# Telemetria_Alimenta_o___Reset.net
KiCad netlist of a schematic drawn in Altium Designer
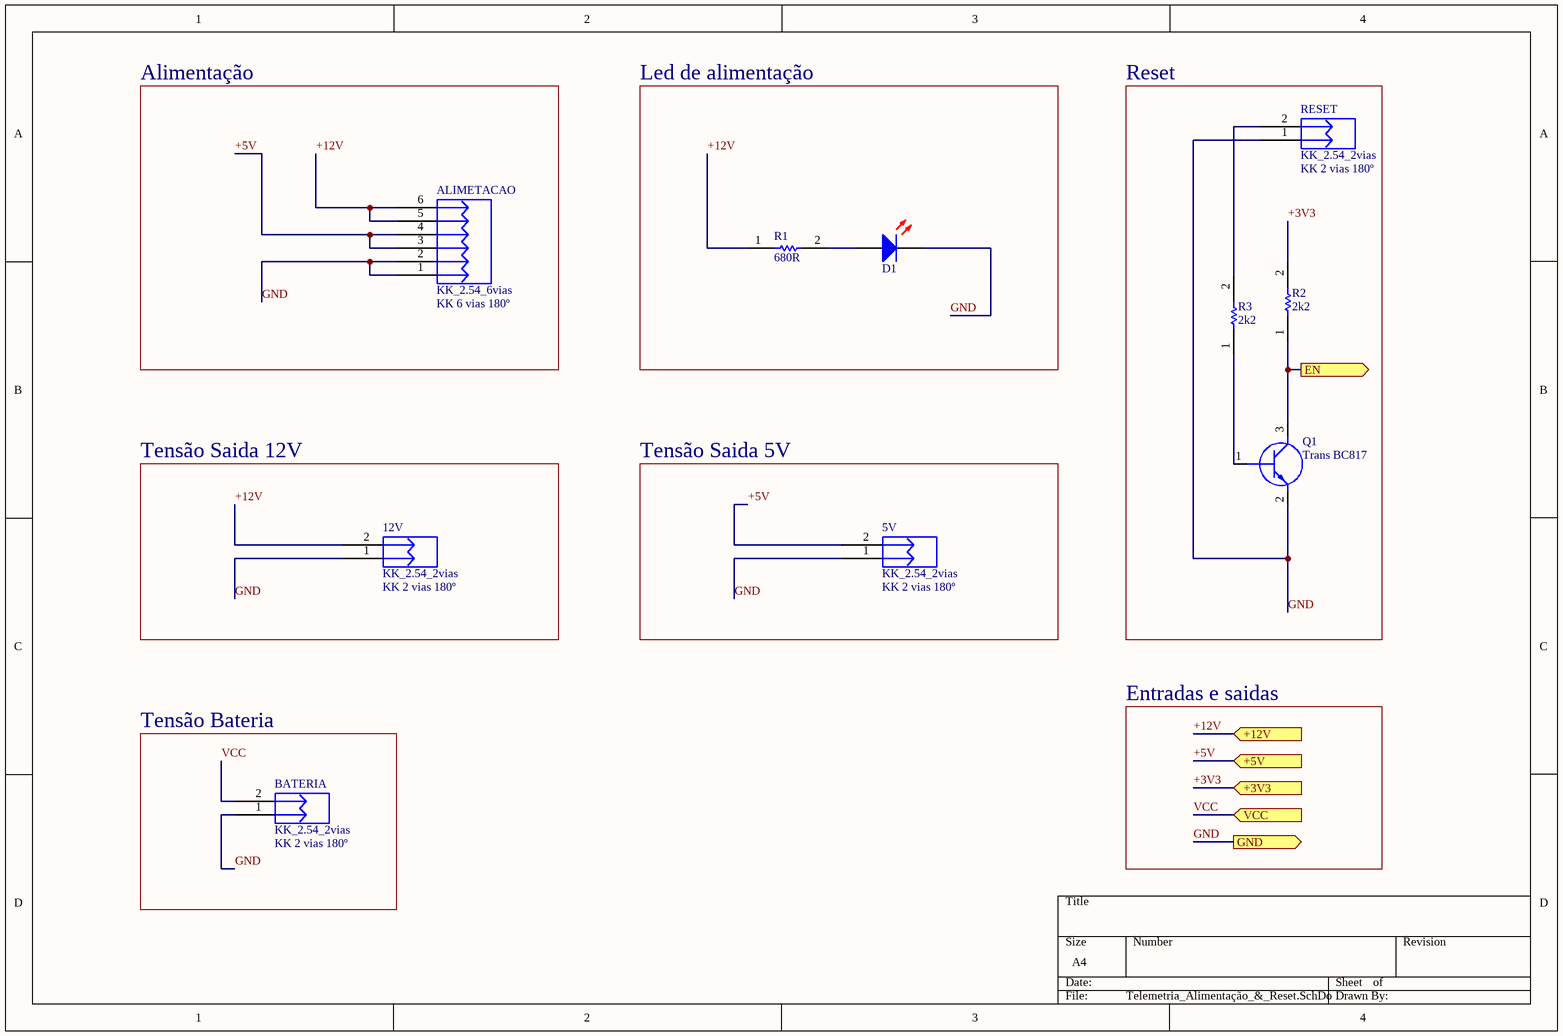
[diagram p0: Telemetria_Alimentação_&_Reset.SchDoc]

(export (version "E")
  (design (tool "Eeschema 10.0.6"))
  (components
    (comp (ref "5V")
      (value "KK_2.54_2vias")
      (footprint "KK_2VIAS_180º")
      (description "Conector KK 2.54mm 2 vias")
      (fields (field (name "VALOR") "KK 2 vias 180º"))
      (libsource (lib "Sinaliza玢o_Official") (part "KK_2.54_2vias"))
    )
    (comp (ref "12V")
      (value "KK_2.54_2vias")
      (footprint "KK_2VIAS_180º")
      (description "Conector KK 2.54mm 2 vias")
      (fields (field (name "VALOR") "KK 2 vias 180º"))
      (libsource (lib "Sinaliza玢o_Official") (part "KK_2.54_2vias"))
    )
    (comp (ref "ALIMETACAO")
      (value "KK_2.54_6vias")
      (footprint "KK_6vias_180°")
      (description "Conector KK 2.54mm 6 vias")
      (fields (field (name "VALOR") "KK 6 vias 180º"))
      (libsource (lib "Sinaliza玢o_Official") (part "KK_2.54_6vias"))
    )
    (comp (ref "BATERIA")
      (value "KK_2.54_2vias")
      (footprint "KK_2VIAS_180º")
      (description "Conector KK 2.54mm 2 vias")
      (fields (field (name "VALOR") "KK 2 vias 180º"))
      (libsource (lib "Conectores_Sch") (part "KK_2.54_2vias"))
    )
    (comp (ref "D1")
      (value "LED 3MM RED")
      (footprint "LED RED")
      (fields (field (name "MANUFACTURER") "Paralight") (field (name "MANUFACTURER PART NUMBER") "IMP585"))
      (libsource (lib "Sinaliza玢o_Official") (part "LED 3MM RED"))
    )
    (comp (ref "Q1")
      (value "Trans BC817")
      (footprint "SOT96P240X110-3N")
      (description "Transistor BJT NPN BC817-25-7-F")
      (fields
        (field (name "MANUFACTURER_PART_NUMBER") "BC817-25-7-F")
        (field (name "MOUSER PART NUMBER") "621-BC817-25-7-F")
      )
      (libsource (lib "Sinaliza玢o_Official") (part "Trans BC817"))
    )
    (comp (ref "R1")
      (value "680R")
      (footprint "RESC3216X60N")
      (description "Resistor")
      (fields
        (field (name "MANUFACTURER_PART_NUMBER") "CRCW12064K70FKEA")
        (field (name "MOUSER PART NUMBER") "71-CRCW1206-4.7K-E3")
      )
      (libsource (lib "Sinaliza玢o_Official") (part "Resistor 1206"))
    )
    (comp (ref "R2")
      (value "2k2")
      (footprint "RESC3216X60N")
      (description "Resistor")
      (fields
        (field (name "MANUFACTURER_PART_NUMBER") "CRCW12064K70FKEA")
        (field (name "MOUSER PART NUMBER") "71-CRCW1206-4.7K-E3")
      )
      (libsource (lib "Sinaliza玢o_Official") (part "Resistor 1206"))
    )
    (comp (ref "R3")
      (value "2k2")
      (footprint "RESC3216X60N")
      (description "Resistor")
      (fields
        (field (name "MANUFACTURER_PART_NUMBER") "CRCW12064K70FKEA")
        (field (name "MOUSER PART NUMBER") "71-CRCW1206-4.7K-E3")
      )
      (libsource (lib "Sinaliza玢o_Official") (part "Resistor 1206"))
    )
    (comp (ref "RESET")
      (value "KK_2.54_2vias")
      (footprint "KK_2VIAS_180º")
      (description "Conector KK 2.54mm 2 vias")
      (fields (field (name "VALOR") "KK 2 vias 180º"))
      (libsource (lib "Sinaliza玢o_Official") (part "KK_2.54_2vias"))
    )
  )
  (nets
    (net (code "1") (name "/+3V3") (class "Default")
      (node (ref "R2") (pin "2") (pinfunction "2_2") (pintype "passive"))
    )
    (net (code "2") (name "/+5V") (class "Default")
      (node (ref "5V") (pin "2") (pintype "passive"))
      (node (ref "ALIMETACAO") (pin "3") (pintype "passive"))
      (node (ref "ALIMETACAO") (pin "4") (pintype "passive"))
    )
    (net (code "3") (name "/+12V") (class "Default")
      (node (ref "12V") (pin "2") (pintype "passive"))
      (node (ref "ALIMETACAO") (pin "5") (pintype "passive"))
      (node (ref "ALIMETACAO") (pin "6") (pintype "passive"))
      (node (ref "R1") (pin "1") (pinfunction "1_1") (pintype "passive"))
    )
    (net (code "4") (name "/EN") (class "Default")
      (node (ref "Q1") (pin "3") (pinfunction "C_3") (pintype "passive"))
      (node (ref "R2") (pin "1") (pinfunction "1_1") (pintype "passive"))
    )
    (net (code "5") (name "/GND") (class "Default")
      (node (ref "12V") (pin "1") (pintype "passive"))
      (node (ref "5V") (pin "1") (pintype "passive"))
      (node (ref "ALIMETACAO") (pin "1") (pintype "passive"))
      (node (ref "ALIMETACAO") (pin "2") (pintype "passive"))
      (node (ref "BATERIA") (pin "1") (pintype "passive"))
      (node (ref "D1") (pin "2") (pinfunction "K_2") (pintype "passive"))
      (node (ref "Q1") (pin "2") (pinfunction "E_2") (pintype "passive"))
      (node (ref "RESET") (pin "1") (pintype "passive"))
    )
    (net (code "6") (name "/VCC") (class "Default") (node (ref "BATERIA") (pin "2") (pintype "passive")))
    (net (code "7") (name "Net-(D1-A)") (class "Default")
      (node (ref "D1") (pin "1") (pinfunction "A_1") (pintype "passive"))
      (node (ref "R1") (pin "2") (pinfunction "2_2") (pintype "passive"))
    )
    (net (code "8") (name "Net-(Q1-B)") (class "Default")
      (node (ref "Q1") (pin "1") (pinfunction "B_1") (pintype "passive"))
      (node (ref "R3") (pin "1") (pinfunction "1_1") (pintype "passive"))
    )
    (net (code "9") (name "Net-(R3-Pad2)") (class "Default")
      (node (ref "R3") (pin "2") (pinfunction "2_2") (pintype "passive"))
      (node (ref "RESET") (pin "2") (pintype "passive"))
    )
  )
)
